# ART-Pi_Connector.net
KiCad netlist of a schematic drawn in Altium Designer
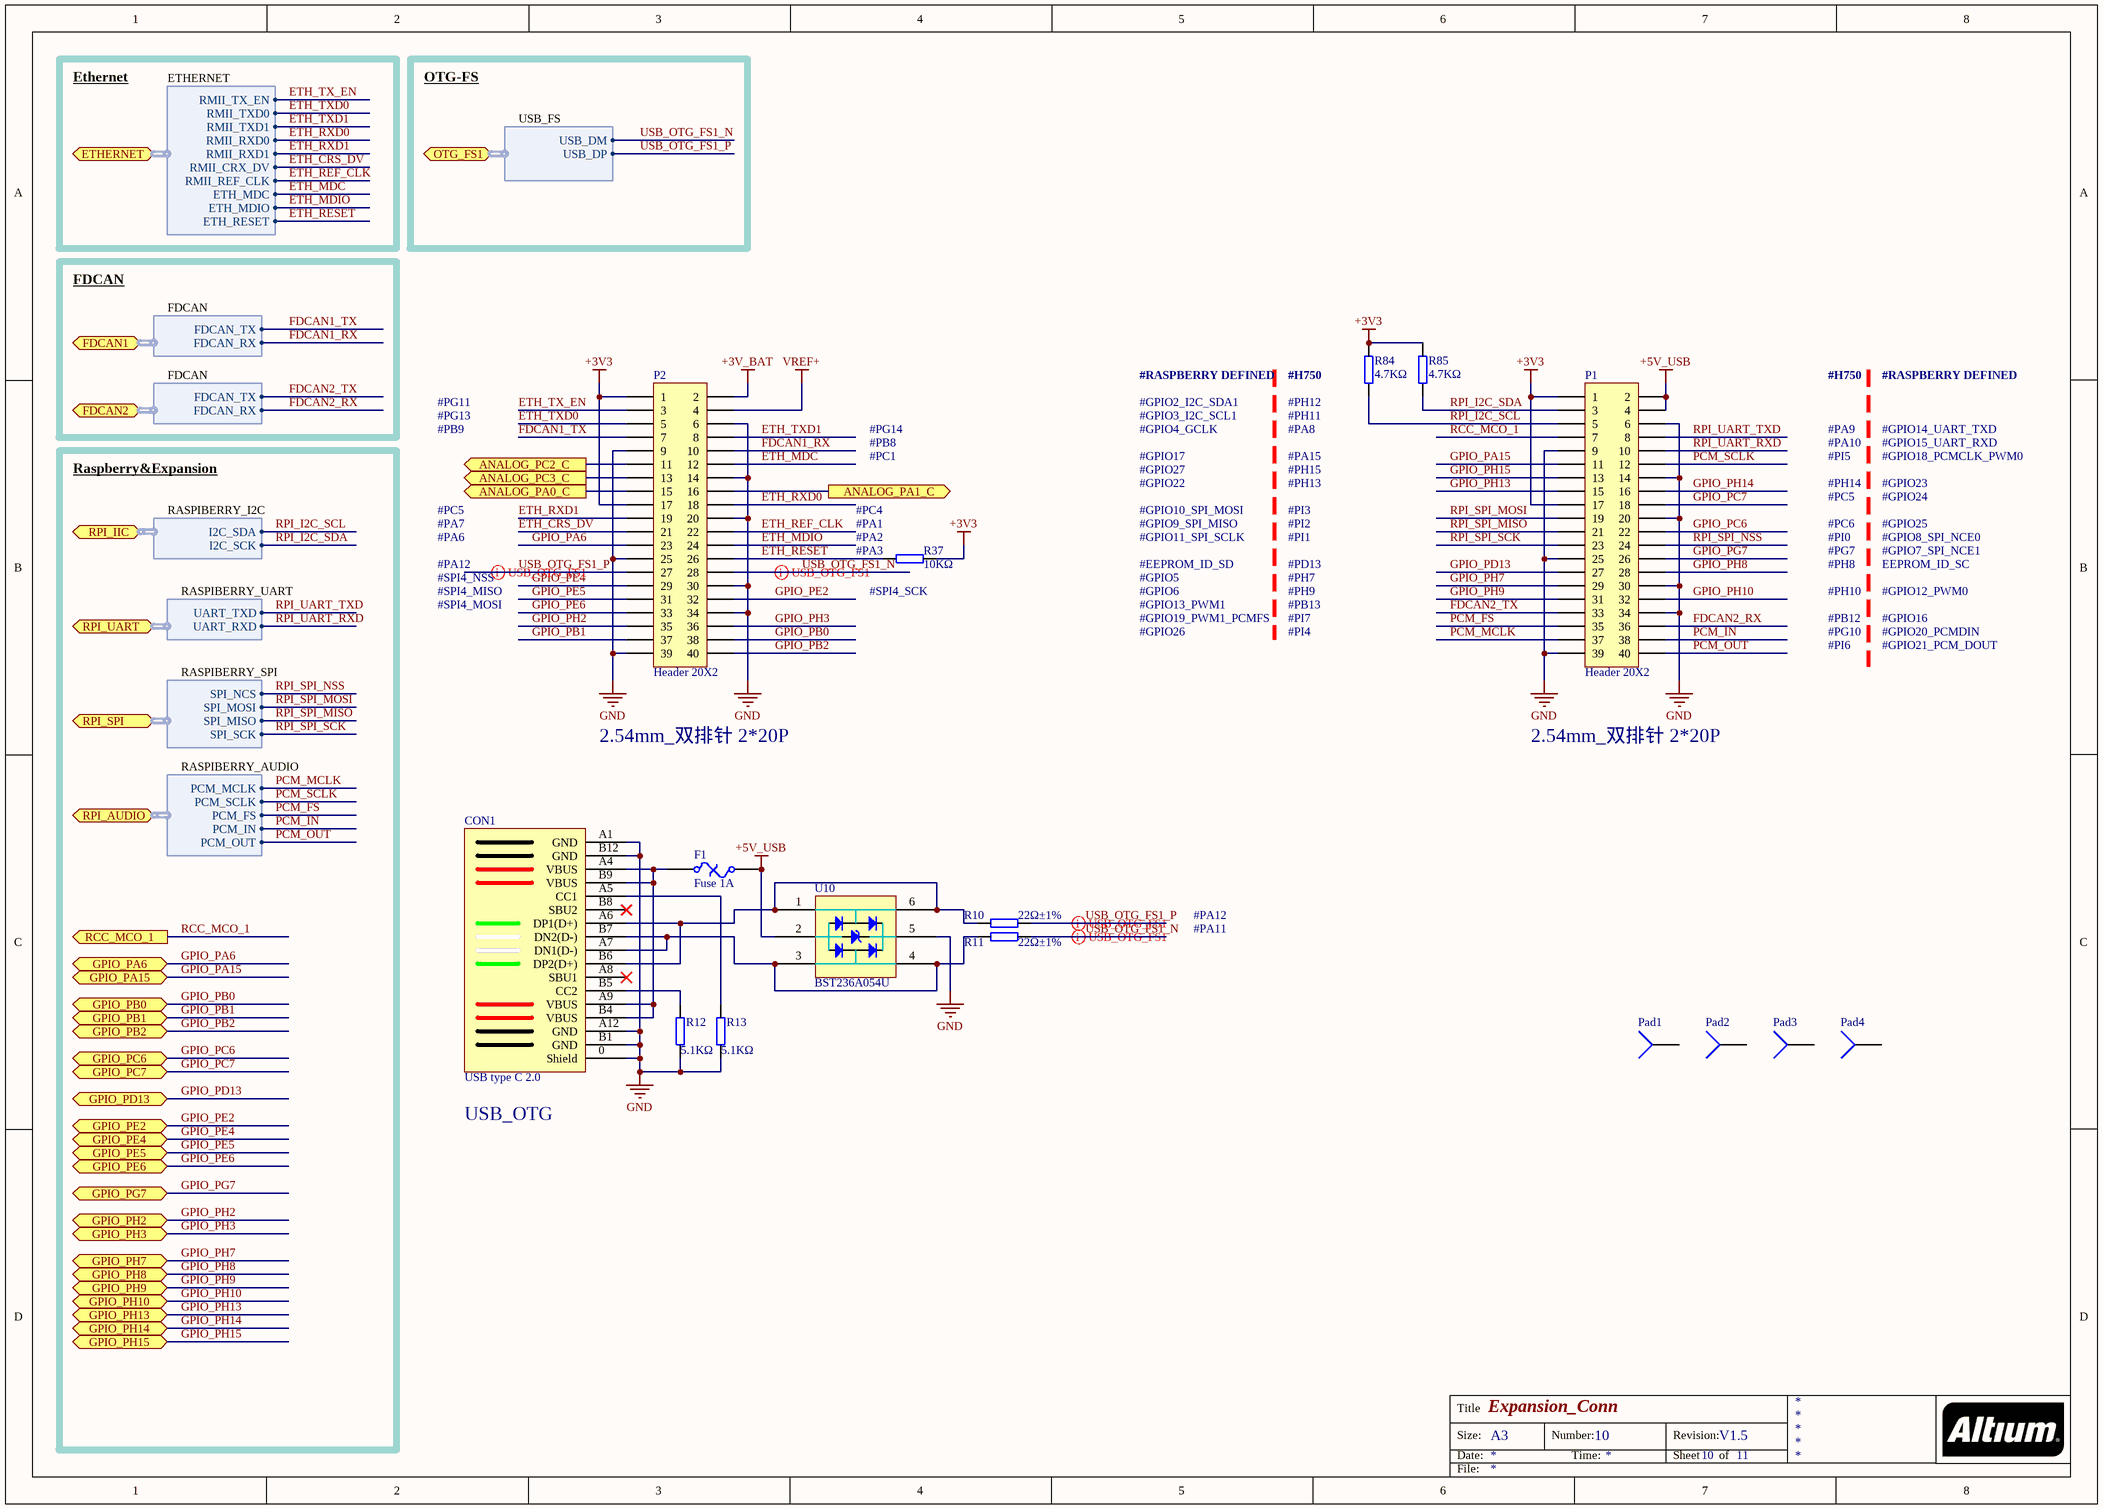
[diagram p0: ART-Pi_Connector.SchDoc]

(export (version "E")
  (design (tool "Eeschema 10.0.6"))
  (components
    (comp (ref "CON1")
      (value "USB type C 2.0")
      (footprint "USB_C")
      (libsource (lib "ART-Pi_STM32H750_COPY") (part "USB type C"))
    )
    (comp (ref "F1")
      (value "Fuse 1A")
      (footprint "0805_R")
      (description "Thermal Fuse")
      (fields (field (name "PUBLISHER") "Altium Limited"))
      (libsource (lib "Miscellaneous Devices") (part "Fuse Thermal"))
    )
    (comp (ref "P1")
      (value "Header 20X2")
      (footprint "HDR2X20")
      (description "Header, 20-Pin, Dual row")
      (fields (field (name "PUBLISHER") "Altium Limited"))
      (libsource (lib "Miscellaneous Connectors") (part "Header 20X2"))
    )
    (comp (ref "P2")
      (value "Header 20X2")
      (footprint "HDR2X20")
      (description "Header, 20-Pin, Dual row")
      (fields (field (name "PUBLISHER") "Altium Limited"))
      (libsource (lib "Miscellaneous Connectors") (part "Header 20X2"))
    )
    (comp (ref "Pad1")
      (value "Socket")
      (footprint "Pad-3mm")
      (fields (field (name "PUBLISHER") "Altium Limited"))
      (libsource (lib "Miscellaneous Connectors") (part "Socket"))
    )
    (comp (ref "Pad2")
      (value "Socket")
      (footprint "Pad-3mm")
      (fields (field (name "PUBLISHER") "Altium Limited"))
      (libsource (lib "Miscellaneous Connectors") (part "Socket"))
    )
    (comp (ref "Pad3")
      (value "Socket")
      (footprint "Pad-3mm")
      (fields (field (name "PUBLISHER") "Altium Limited"))
      (libsource (lib "Miscellaneous Connectors") (part "Socket"))
    )
    (comp (ref "Pad4")
      (value "Socket")
      (footprint "Pad-3mm")
      (fields (field (name "PUBLISHER") "Altium Limited"))
      (libsource (lib "Miscellaneous Connectors") (part "Socket"))
    )
    (comp (ref "R10")
      (value "22Ω±1%")
      (footprint "0402_R")
      (description "Resister")
      (libsource (lib "ART-Pi_STM32H750_COPY") (part "Res"))
    )
    (comp (ref "R11")
      (value "22Ω±1%")
      (footprint "0402_R")
      (description "Resister")
      (libsource (lib "ART-Pi_STM32H750_COPY") (part "Res"))
    )
    (comp (ref "R12")
      (value "5.1KΩ")
      (footprint "0402_R")
      (description "Resister")
      (libsource (lib "ART-Pi_STM32H750_COPY") (part "Res"))
    )
    (comp (ref "R13")
      (value "5.1KΩ")
      (footprint "0402_R")
      (description "Resister")
      (libsource (lib "ART-Pi_STM32H750_COPY") (part "Res"))
    )
    (comp (ref "R37")
      (value "10KΩ")
      (footprint "0402_R")
      (description "Resister")
      (libsource (lib "ART-Pi_STM32H750_COPY") (part "Res"))
    )
    (comp (ref "R84")
      (value "4.7KΩ")
      (footprint "0402_R")
      (description "Resister")
      (libsource (lib "ART-Pi_STM32H750_COPY") (part "Res"))
    )
    (comp (ref "R85")
      (value "4.7KΩ")
      (footprint "0402_R")
      (description "Resister")
      (libsource (lib "ART-Pi_STM32H750_COPY") (part "Res"))
    )
    (comp (ref "U10")
      (value "BST236A054U")
      (footprint "SOT23_6")
      (libsource (lib "ART-Pi_STM32H750_COPY") (part "BST236A054U"))
    )
  )
  (nets
    (net (code "2") (name "+3V3") (class "Default")
      (node (ref "P1") (pin "1") (pinfunction "1_1") (pintype "passive"))
      (node (ref "P1") (pin "17") (pinfunction "17_17") (pintype "passive"))
      (node (ref "P2") (pin "1") (pinfunction "1_1") (pintype "passive"))
      (node (ref "P2") (pin "17") (pinfunction "17_17") (pintype "passive"))
      (node (ref "R37") (pin "1") (pinfunction "1_1") (pintype "passive"))
      (node (ref "R84") (pin "1") (pinfunction "1_1") (pintype "passive"))
      (node (ref "R85") (pin "1") (pinfunction "1_1") (pintype "passive"))
    )
    (net (code "3") (name "+3V_BAT") (class "Default")
      (node (ref "P2") (pin "2") (pinfunction "2_2") (pintype "passive"))
    )
    (net (code "4") (name "+5V_USB") (class "Default")
      (node (ref "F1") (pin "2") (pinfunction "2_2") (pintype "passive"))
      (node (ref "P1") (pin "2") (pinfunction "2_2") (pintype "passive"))
      (node (ref "P1") (pin "4") (pinfunction "4_4") (pintype "passive"))
      (node (ref "U10") (pin "2") (pinfunction "2_2") (pintype "passive"))
    )
    (net (code "5") (name "/ANALOG_PA0_C") (class "Default")
      (node (ref "P2") (pin "15") (pinfunction "15_15") (pintype "passive"))
    )
    (net (code "6") (name "/ANALOG_PA1_C") (class "Default")
      (node (ref "P2") (pin "16") (pinfunction "16_16") (pintype "passive"))
    )
    (net (code "7") (name "/ANALOG_PC2_C") (class "Default")
      (node (ref "P2") (pin "11") (pinfunction "11_11") (pintype "passive"))
    )
    (net (code "8") (name "/ANALOG_PC3_C") (class "Default")
      (node (ref "P2") (pin "13") (pinfunction "13_13") (pintype "passive"))
    )
    (net (code "9") (name "/ETH_CRS_DV") (class "Default")
      (node (ref "P2") (pin "21") (pinfunction "21_21") (pintype "passive"))
    )
    (net (code "10") (name "/ETH_MDC") (class "Default")
      (node (ref "P2") (pin "12") (pinfunction "12_12") (pintype "passive"))
    )
    (net (code "11") (name "/ETH_MDIO") (class "Default")
      (node (ref "P2") (pin "24") (pinfunction "24_24") (pintype "passive"))
    )
    (net (code "12") (name "/ETH_REF_CLK") (class "Default")
      (node (ref "P2") (pin "22") (pinfunction "22_22") (pintype "passive"))
    )
    (net (code "13") (name "/ETH_RESET") (class "Default")
      (node (ref "P2") (pin "26") (pinfunction "26_26") (pintype "passive"))
      (node (ref "R37") (pin "2") (pinfunction "2_2") (pintype "passive"))
    )
    (net (code "14") (name "/ETH_RXD0") (class "Default")
      (node (ref "P2") (pin "18") (pinfunction "18_18") (pintype "passive"))
    )
    (net (code "15") (name "/ETH_RXD1") (class "Default")
      (node (ref "P2") (pin "19") (pinfunction "19_19") (pintype "passive"))
    )
    (net (code "16") (name "/ETH_TXD0") (class "Default")
      (node (ref "P2") (pin "5") (pinfunction "5_5") (pintype "passive"))
    )
    (net (code "17") (name "/ETH_TXD1") (class "Default")
      (node (ref "P2") (pin "8") (pinfunction "8_8") (pintype "passive"))
    )
    (net (code "18") (name "/ETH_TX_EN") (class "Default")
      (node (ref "P2") (pin "3") (pinfunction "3_3") (pintype "passive"))
    )
    (net (code "19") (name "/FDCAN1_RX") (class "Default")
      (node (ref "P2") (pin "10") (pinfunction "10_10") (pintype "passive"))
    )
    (net (code "20") (name "/FDCAN1_TX") (class "Default")
      (node (ref "P2") (pin "7") (pinfunction "7_7") (pintype "passive"))
    )
    (net (code "21") (name "/FDCAN2_RX") (class "Default")
      (node (ref "P1") (pin "36") (pinfunction "36_36") (pintype "passive"))
    )
    (net (code "22") (name "/FDCAN2_TX") (class "Default")
      (node (ref "P1") (pin "33") (pinfunction "33_33") (pintype "passive"))
    )
    (net (code "23") (name "/GPIO_PA6") (class "Default")
      (node (ref "P2") (pin "23") (pinfunction "23_23") (pintype "passive"))
    )
    (net (code "24") (name "/GPIO_PA15") (class "Default")
      (node (ref "P1") (pin "11") (pinfunction "11_11") (pintype "passive"))
    )
    (net (code "25") (name "/GPIO_PB0") (class "Default")
      (node (ref "P2") (pin "38") (pinfunction "38_38") (pintype "passive"))
    )
    (net (code "26") (name "/GPIO_PB1") (class "Default")
      (node (ref "P2") (pin "37") (pinfunction "37_37") (pintype "passive"))
    )
    (net (code "27") (name "/GPIO_PB2") (class "Default")
      (node (ref "P2") (pin "40") (pinfunction "40_40") (pintype "passive"))
    )
    (net (code "28") (name "/GPIO_PC6") (class "Default")
      (node (ref "P1") (pin "22") (pinfunction "22_22") (pintype "passive"))
    )
    (net (code "29") (name "/GPIO_PC7") (class "Default")
      (node (ref "P1") (pin "18") (pinfunction "18_18") (pintype "passive"))
    )
    (net (code "30") (name "/GPIO_PD13") (class "Default")
      (node (ref "P1") (pin "27") (pinfunction "27_27") (pintype "passive"))
    )
    (net (code "31") (name "/GPIO_PE2") (class "Default")
      (node (ref "P2") (pin "32") (pinfunction "32_32") (pintype "passive"))
    )
    (net (code "32") (name "/GPIO_PE4") (class "Default")
      (node (ref "P2") (pin "29") (pinfunction "29_29") (pintype "passive"))
    )
    (net (code "33") (name "/GPIO_PE5") (class "Default")
      (node (ref "P2") (pin "31") (pinfunction "31_31") (pintype "passive"))
    )
    (net (code "34") (name "/GPIO_PE6") (class "Default")
      (node (ref "P2") (pin "33") (pinfunction "33_33") (pintype "passive"))
    )
    (net (code "35") (name "/GPIO_PG7") (class "Default")
      (node (ref "P1") (pin "26") (pinfunction "26_26") (pintype "passive"))
    )
    (net (code "36") (name "/GPIO_PH2") (class "Default")
      (node (ref "P2") (pin "35") (pinfunction "35_35") (pintype "passive"))
    )
    (net (code "37") (name "/GPIO_PH3") (class "Default")
      (node (ref "P2") (pin "36") (pinfunction "36_36") (pintype "passive"))
    )
    (net (code "38") (name "/GPIO_PH7") (class "Default")
      (node (ref "P1") (pin "29") (pinfunction "29_29") (pintype "passive"))
    )
    (net (code "39") (name "/GPIO_PH8") (class "Default")
      (node (ref "P1") (pin "28") (pinfunction "28_28") (pintype "passive"))
    )
    (net (code "40") (name "/GPIO_PH9") (class "Default")
      (node (ref "P1") (pin "31") (pinfunction "31_31") (pintype "passive"))
    )
    (net (code "41") (name "/GPIO_PH10") (class "Default")
      (node (ref "P1") (pin "32") (pinfunction "32_32") (pintype "passive"))
    )
    (net (code "42") (name "/GPIO_PH13") (class "Default")
      (node (ref "P1") (pin "15") (pinfunction "15_15") (pintype "passive"))
    )
    (net (code "43") (name "/GPIO_PH14") (class "Default")
      (node (ref "P1") (pin "16") (pinfunction "16_16") (pintype "passive"))
    )
    (net (code "44") (name "/GPIO_PH15") (class "Default")
      (node (ref "P1") (pin "13") (pinfunction "13_13") (pintype "passive"))
    )
    (net (code "45") (name "/PCM_FS") (class "Default")
      (node (ref "P1") (pin "35") (pinfunction "35_35") (pintype "passive"))
    )
    (net (code "46") (name "/PCM_IN") (class "Default")
      (node (ref "P1") (pin "38") (pinfunction "38_38") (pintype "passive"))
    )
    (net (code "47") (name "/PCM_MCLK") (class "Default")
      (node (ref "P1") (pin "37") (pinfunction "37_37") (pintype "passive"))
    )
    (net (code "48") (name "/PCM_OUT") (class "Default")
      (node (ref "P1") (pin "40") (pinfunction "40_40") (pintype "passive"))
    )
    (net (code "49") (name "/PCM_SCLK") (class "Default")
      (node (ref "P1") (pin "12") (pinfunction "12_12") (pintype "passive"))
    )
    (net (code "50") (name "/RCC_MCO_1") (class "Default")
      (node (ref "P1") (pin "7") (pinfunction "7_7") (pintype "passive"))
    )
    (net (code "51") (name "/RPI_I2C_SCL") (class "Default")
      (node (ref "P1") (pin "5") (pinfunction "5_5") (pintype "passive"))
      (node (ref "R84") (pin "2") (pinfunction "2_2") (pintype "passive"))
    )
    (net (code "52") (name "/RPI_I2C_SDA") (class "Default")
      (node (ref "P1") (pin "3") (pinfunction "3_3") (pintype "passive"))
      (node (ref "R85") (pin "2") (pinfunction "2_2") (pintype "passive"))
    )
    (net (code "53") (name "/RPI_SPI_MISO") (class "Default")
      (node (ref "P1") (pin "21") (pinfunction "21_21") (pintype "passive"))
    )
    (net (code "54") (name "/RPI_SPI_MOSI") (class "Default")
      (node (ref "P1") (pin "19") (pinfunction "19_19") (pintype "passive"))
    )
    (net (code "55") (name "/RPI_SPI_NSS") (class "Default")
      (node (ref "P1") (pin "24") (pinfunction "24_24") (pintype "passive"))
    )
    (net (code "56") (name "/RPI_SPI_SCK") (class "Default")
      (node (ref "P1") (pin "23") (pinfunction "23_23") (pintype "passive"))
    )
    (net (code "57") (name "/RPI_UART_RXD") (class "Default")
      (node (ref "P1") (pin "10") (pinfunction "10_10") (pintype "passive"))
    )
    (net (code "58") (name "/RPI_UART_TXD") (class "Default")
      (node (ref "P1") (pin "8") (pinfunction "8_8") (pintype "passive"))
    )
    (net (code "59") (name "/USB_OTG_FS1_N") (class "Default")
      (node (ref "P2") (pin "28") (pinfunction "28_28") (pintype "passive"))
      (node (ref "R11") (pin "2") (pinfunction "2_2") (pintype "passive"))
    )
    (net (code "60") (name "/USB_OTG_FS1_P") (class "Default")
      (node (ref "P2") (pin "27") (pinfunction "27_27") (pintype "passive"))
      (node (ref "R10") (pin "2") (pinfunction "2_2") (pintype "passive"))
    )
    (net (code "62") (name "GND") (class "Default")
      (node (ref "CON1") (pin "0") (pinfunction "Shield_0") (pintype "passive"))
      (node (ref "CON1") (pin "A1") (pinfunction "GND_A1") (pintype "passive"))
      (node (ref "CON1") (pin "A12") (pinfunction "GND_A12") (pintype "passive"))
      (node (ref "CON1") (pin "B1") (pinfunction "GND_B1") (pintype "passive"))
      (node (ref "CON1") (pin "B12") (pinfunction "GND_B12") (pintype "passive"))
      (node (ref "P1") (pin "14") (pinfunction "14_14") (pintype "passive"))
      (node (ref "P1") (pin "20") (pinfunction "20_20") (pintype "passive"))
      (node (ref "P1") (pin "25") (pinfunction "25_25") (pintype "passive"))
      (node (ref "P1") (pin "30") (pinfunction "30_30") (pintype "passive"))
      (node (ref "P1") (pin "34") (pinfunction "34_34") (pintype "passive"))
      (node (ref "P1") (pin "39") (pinfunction "39_39") (pintype "passive"))
      (node (ref "P1") (pin "6") (pinfunction "6_6") (pintype "passive"))
      (node (ref "P1") (pin "9") (pinfunction "9_9") (pintype "passive"))
      (node (ref "P2") (pin "14") (pinfunction "14_14") (pintype "passive"))
      (node (ref "P2") (pin "20") (pinfunction "20_20") (pintype "passive"))
      (node (ref "P2") (pin "25") (pinfunction "25_25") (pintype "passive"))
      (node (ref "P2") (pin "30") (pinfunction "30_30") (pintype "passive"))
      (node (ref "P2") (pin "34") (pinfunction "34_34") (pintype "passive"))
      (node (ref "P2") (pin "39") (pinfunction "39_39") (pintype "passive"))
      (node (ref "P2") (pin "6") (pinfunction "6_6") (pintype "passive"))
      (node (ref "P2") (pin "9") (pinfunction "9_9") (pintype "passive"))
      (node (ref "R12") (pin "2") (pinfunction "2_2") (pintype "passive"))
      (node (ref "R13") (pin "2") (pinfunction "2_2") (pintype "passive"))
      (node (ref "U10") (pin "5") (pinfunction "5_5") (pintype "passive"))
    )
    (net (code "63") (name "Net-(CON1-CC1)") (class "Default")
      (node (ref "CON1") (pin "A5") (pinfunction "CC1_A5") (pintype "passive"))
      (node (ref "R13") (pin "1") (pinfunction "1_1") (pintype "passive"))
    )
    (net (code "64") (name "Net-(CON1-CC2)") (class "Default")
      (node (ref "CON1") (pin "B5") (pinfunction "CC2_B5") (pintype "passive"))
      (node (ref "R12") (pin "1") (pinfunction "1_1") (pintype "passive"))
    )
    (net (code "65") (name "Net-(CON1-DN1(D-))") (class "Default")
      (node (ref "CON1") (pin "A7") (pinfunction "DN1(D-)_A7") (pintype "passive"))
      (node (ref "CON1") (pin "B7") (pinfunction "DN2(D-)_B7") (pintype "passive"))
      (node (ref "R11") (pin "1") (pinfunction "1_1") (pintype "passive"))
      (node (ref "U10") (pin "3") (pinfunction "3_3") (pintype "passive"))
      (node (ref "U10") (pin "4") (pinfunction "4_4") (pintype "passive"))
    )
    (net (code "66") (name "Net-(CON1-DP1(D+))") (class "Default")
      (node (ref "CON1") (pin "A6") (pinfunction "DP1(D+)_A6") (pintype "passive"))
      (node (ref "CON1") (pin "B6") (pinfunction "DP2(D+)_B6") (pintype "passive"))
      (node (ref "R10") (pin "1") (pinfunction "1_1") (pintype "passive"))
      (node (ref "U10") (pin "1") (pinfunction "1_1") (pintype "passive"))
      (node (ref "U10") (pin "6") (pinfunction "6_6") (pintype "passive"))
    )
    (net (code "67") (name "Net-(CON1-VBUS-PadA4)") (class "Default")
      (node (ref "CON1") (pin "A4") (pinfunction "VBUS_A4") (pintype "passive"))
      (node (ref "CON1") (pin "A9") (pinfunction "VBUS_A9") (pintype "passive"))
      (node (ref "CON1") (pin "B4") (pinfunction "VBUS_B4") (pintype "passive"))
      (node (ref "CON1") (pin "B9") (pinfunction "VBUS_B9") (pintype "passive"))
      (node (ref "F1") (pin "1") (pinfunction "1_1") (pintype "passive"))
    )
    (net (code "68") (name "VREF+") (class "Default")
      (node (ref "P2") (pin "4") (pinfunction "4_4") (pintype "passive"))
    )
    (net (code "69") (name "unconnected-(CON1-SBU1-PadA8)") (class "Default")
      (node (ref "CON1") (pin "A8") (pinfunction "SBU1_A8") (pintype "passive+no_connect"))
    )
    (net (code "70") (name "unconnected-(CON1-SBU2-PadB8)") (class "Default")
      (node (ref "CON1") (pin "B8") (pinfunction "SBU2_B8") (pintype "passive+no_connect"))
    )
    (net (code "71") (name "unconnected-(Pad1-Pad0)") (class "Default")
      (node (ref "Pad1") (pin "0") (pinfunction "0_0") (pintype "passive"))
    )
    (net (code "72") (name "unconnected-(Pad2-Pad0)") (class "Default")
      (node (ref "Pad2") (pin "0") (pinfunction "0_0") (pintype "passive"))
    )
    (net (code "73") (name "unconnected-(Pad3-Pad0)") (class "Default")
      (node (ref "Pad3") (pin "0") (pinfunction "0_0") (pintype "passive"))
    )
    (net (code "74") (name "unconnected-(Pad4-Pad0)") (class "Default")
      (node (ref "Pad4") (pin "0") (pinfunction "0_0") (pintype "passive"))
    )
  )
)
